# GainDrain.net
KiCad netlist of a schematic drawn in Altium Designer
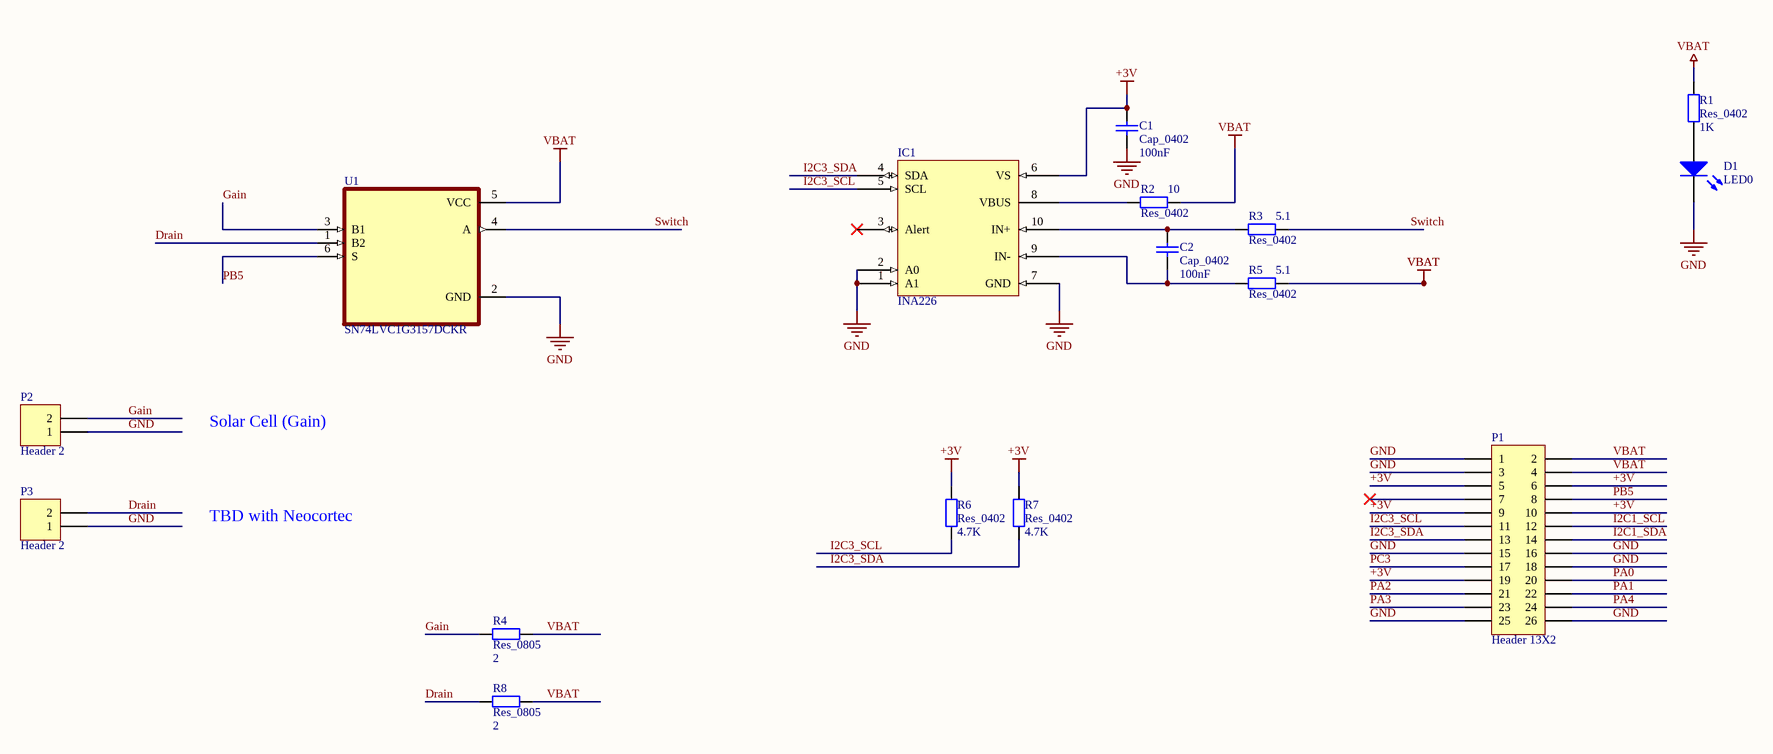
[diagram p0: GainDrain.SchDoc]

(export (version "E")
  (design (tool "Eeschema 10.0.6"))
  (components
    (comp (ref "C1")
      (value "Cap_0402")
      (footprint "0402")
      (description "Capacitor")
      (fields (field (name "ALTIUM_VALUE") "100nF") (field (name "PUBLISHER") "Altium Limited"))
      (libsource (lib "Schematic_Components") (part "Cap_0402"))
    )
    (comp (ref "C2")
      (value "Cap_0402")
      (footprint "0402")
      (description "Capacitor")
      (fields (field (name "ALTIUM_VALUE") "100nF") (field (name "PUBLISHER") "Altium Limited"))
      (libsource (lib "Schematic_Components") (part "Cap_0402"))
    )
    (comp (ref "D1")
      (value "LED0")
      (footprint "0603")
      (description "Typical INFRARED GaAs LED")
      (fields (field (name "PUBLISHER") "Altium Limited"))
      (libsource (lib "Schematic_Components") (part "LED0"))
    )
    (comp (ref "IC1")
      (value "INA226")
      (footprint "VSSOP-10")
      (description "Bi-Directional Current and Power Monitor")
      (libsource (lib "Schematic_Components") (part "INA226"))
    )
    (comp (ref "P1")
      (value "Header 13X2")
      (footprint "HDR2X13")
      (description "Header, 13-Pin, Dual row")
      (fields (field (name "PUBLISHER") "Altium Limited"))
      (libsource (lib "Miscellaneous Connectors") (part "Header 13X2"))
    )
    (comp (ref "P2")
      (value "Header 2")
      (footprint "HDR1X2")
      (description "Header, 2-Pin")
      (fields (field (name "PUBLISHER") "Altium Limited"))
      (libsource (lib "Miscellaneous Connectors") (part "Header 2"))
    )
    (comp (ref "P3")
      (value "Header 2")
      (footprint "HDR1X2")
      (description "Header, 2-Pin")
      (fields (field (name "PUBLISHER") "Altium Limited"))
      (libsource (lib "Miscellaneous Connectors") (part "Header 2"))
    )
    (comp (ref "R1")
      (value "Res_0402")
      (footprint "0402")
      (description "Resistor")
      (fields (field (name "ALTIUM_VALUE") "1K") (field (name "PUBLISHER") "Altium Limited"))
      (libsource (lib "Schematic_Components") (part "Res_0402"))
    )
    (comp (ref "R2")
      (value "Res_0402")
      (footprint "0402")
      (description "Resistor")
      (fields (field (name "ALTIUM_VALUE") "10") (field (name "PUBLISHER") "Altium Limited"))
      (libsource (lib "") (part "Res_0402_1"))
    )
    (comp (ref "R3")
      (value "Res_0402")
      (footprint "0402")
      (description "Resistor")
      (fields (field (name "ALTIUM_VALUE") "5.1") (field (name "PUBLISHER") "Altium Limited"))
      (libsource (lib "") (part "Res_0402_1"))
    )
    (comp (ref "R4")
      (value "Res_0805")
      (footprint "0805")
      (description "Resistor")
      (fields (field (name "ALTIUM_VALUE") "2") (field (name "PUBLISHER") "Altium Limited"))
      (libsource (lib "Schematic_Components") (part "Res_0805"))
    )
    (comp (ref "R5")
      (value "Res_0402")
      (footprint "0402")
      (description "Resistor")
      (fields (field (name "ALTIUM_VALUE") "5.1") (field (name "PUBLISHER") "Altium Limited"))
      (libsource (lib "") (part "Res_0402_1"))
    )
    (comp (ref "R6")
      (value "Res_0402")
      (footprint "0402")
      (description "Resistor")
      (fields (field (name "ALTIUM_VALUE") "4.7K") (field (name "PUBLISHER") "Altium Limited"))
      (libsource (lib "Schematic_Components") (part "Res_0402"))
    )
    (comp (ref "R7")
      (value "Res_0402")
      (footprint "0402")
      (description "Resistor")
      (fields (field (name "ALTIUM_VALUE") "4.7K") (field (name "PUBLISHER") "Altium Limited"))
      (libsource (lib "Schematic_Components") (part "Res_0402"))
    )
    (comp (ref "R8")
      (value "Res_0805")
      (footprint "0805")
      (description "Resistor")
      (fields (field (name "ALTIUM_VALUE") "2") (field (name "PUBLISHER") "Altium Limited"))
      (libsource (lib "Schematic_Components") (part "Res_0805"))
    )
    (comp (ref "U1")
      (value "SN74LVC1G3157DCKR")
      (footprint "SOT65P210X110-6N")
      (description "5 Vï¼Œ2ï¼š1ï¼ˆSPDTï¼‰ï¼Œ1é€šé“é€šç”¨æ¨¡æ“¬é–‹é—œ6-SC70 -40è‡³125")
      (fields (field (name "MF") "Texas Instruments"))
      (libsource (lib "SN74LVC1G3157DCKR") (part "SN74LVC1G3157DCKR"))
    )
  )
  (nets
    (net (code "1") (name "+3V") (class "Default")
      (node (ref "C1") (pin "2") (pinfunction "2_2") (pintype "passive"))
      (node (ref "IC1") (pin "6") (pinfunction "VS_6") (pintype "input"))
      (node (ref "P1") (pin "10") (pinfunction "10_10") (pintype "passive"))
      (node (ref "P1") (pin "19") (pinfunction "19_19") (pintype "passive"))
      (node (ref "P1") (pin "5") (pinfunction "5_5") (pintype "passive"))
      (node (ref "P1") (pin "6") (pinfunction "6_6") (pintype "passive"))
      (node (ref "P1") (pin "9") (pinfunction "9_9") (pintype "passive"))
      (node (ref "R6") (pin "2") (pinfunction "2_2") (pintype "passive"))
      (node (ref "R7") (pin "2") (pinfunction "2_2") (pintype "passive"))
    )
    (net (code "2") (name "/Drain") (class "Default")
      (node (ref "P3") (pin "2") (pinfunction "2_2") (pintype "passive"))
      (node (ref "R8") (pin "2") (pinfunction "2_2") (pintype "passive"))
      (node (ref "U1") (pin "1") (pinfunction "B2_1") (pintype "input"))
    )
    (net (code "3") (name "/Gain") (class "Default")
      (node (ref "P2") (pin "2") (pinfunction "2_2") (pintype "passive"))
      (node (ref "R4") (pin "2") (pinfunction "2_2") (pintype "passive"))
      (node (ref "U1") (pin "3") (pinfunction "B1_3") (pintype "input"))
    )
    (net (code "4") (name "/I2C1_SCL") (class "Default")
      (node (ref "P1") (pin "12") (pinfunction "12_12") (pintype "passive"))
    )
    (net (code "5") (name "/I2C1_SDA") (class "Default")
      (node (ref "P1") (pin "14") (pinfunction "14_14") (pintype "passive"))
    )
    (net (code "6") (name "/I2C3_SCL") (class "Default")
      (node (ref "IC1") (pin "5") (pinfunction "SCL_5") (pintype "input"))
      (node (ref "P1") (pin "11") (pinfunction "11_11") (pintype "passive"))
      (node (ref "R6") (pin "1") (pinfunction "1_1") (pintype "passive"))
    )
    (net (code "7") (name "/I2C3_SDA") (class "Default")
      (node (ref "IC1") (pin "4") (pinfunction "SDA_4") (pintype "bidirectional"))
      (node (ref "P1") (pin "13") (pinfunction "13_13") (pintype "passive"))
      (node (ref "R7") (pin "1") (pinfunction "1_1") (pintype "passive"))
    )
    (net (code "8") (name "/PA0") (class "Default")
      (node (ref "P1") (pin "20") (pinfunction "20_20") (pintype "passive"))
    )
    (net (code "9") (name "/PA1") (class "Default")
      (node (ref "P1") (pin "22") (pinfunction "22_22") (pintype "passive"))
    )
    (net (code "10") (name "/PA2") (class "Default")
      (node (ref "P1") (pin "21") (pinfunction "21_21") (pintype "passive"))
    )
    (net (code "11") (name "/PA3") (class "Default")
      (node (ref "P1") (pin "23") (pinfunction "23_23") (pintype "passive"))
    )
    (net (code "12") (name "/PA4") (class "Default")
      (node (ref "P1") (pin "24") (pinfunction "24_24") (pintype "passive"))
    )
    (net (code "13") (name "/PB5") (class "Default")
      (node (ref "P1") (pin "8") (pinfunction "8_8") (pintype "passive"))
      (node (ref "U1") (pin "6") (pinfunction "S_6") (pintype "input"))
    )
    (net (code "14") (name "/PC3") (class "Default")
      (node (ref "P1") (pin "17") (pinfunction "17_17") (pintype "passive"))
    )
    (net (code "15") (name "/Switch") (class "Default")
      (node (ref "R3") (pin "2") (pinfunction "2_2") (pintype "passive"))
      (node (ref "U1") (pin "4") (pinfunction "A_4") (pintype "output"))
    )
    (net (code "16") (name "GND") (class "Default")
      (node (ref "C1") (pin "1") (pinfunction "1_1") (pintype "passive"))
      (node (ref "D1") (pin "1") (pinfunction "K_1") (pintype "passive"))
      (node (ref "IC1") (pin "1") (pinfunction "A1_1") (pintype "input"))
      (node (ref "IC1") (pin "2") (pinfunction "A0_2") (pintype "input"))
      (node (ref "IC1") (pin "7") (pinfunction "GND_7") (pintype "input"))
      (node (ref "P1") (pin "1") (pinfunction "1_1") (pintype "passive"))
      (node (ref "P1") (pin "15") (pinfunction "15_15") (pintype "passive"))
      (node (ref "P1") (pin "16") (pinfunction "16_16") (pintype "passive"))
      (node (ref "P1") (pin "18") (pinfunction "18_18") (pintype "passive"))
      (node (ref "P1") (pin "25") (pinfunction "25_25") (pintype "passive"))
      (node (ref "P1") (pin "26") (pinfunction "26_26") (pintype "passive"))
      (node (ref "P1") (pin "3") (pinfunction "3_3") (pintype "passive"))
      (node (ref "P2") (pin "1") (pinfunction "1_1") (pintype "passive"))
      (node (ref "P3") (pin "1") (pinfunction "1_1") (pintype "passive"))
      (node (ref "U1") (pin "2") (pinfunction "GND_2") (pintype "power_in"))
    )
    (net (code "17") (name "Net-(D1-A)") (class "Default")
      (node (ref "D1") (pin "2") (pinfunction "A_2") (pintype "passive"))
      (node (ref "R1") (pin "1") (pinfunction "1_1") (pintype "passive"))
    )
    (net (code "18") (name "Net-(IC1-IN+)") (class "Default")
      (node (ref "C2") (pin "2") (pinfunction "2_2") (pintype "passive"))
      (node (ref "IC1") (pin "10") (pinfunction "IN+_10") (pintype "input"))
      (node (ref "R3") (pin "1") (pinfunction "1_1") (pintype "passive"))
    )
    (net (code "19") (name "Net-(IC1-IN-)") (class "Default")
      (node (ref "C2") (pin "1") (pinfunction "1_1") (pintype "passive"))
      (node (ref "IC1") (pin "9") (pinfunction "IN-_9") (pintype "input"))
      (node (ref "R5") (pin "1") (pinfunction "1_1") (pintype "passive"))
    )
    (net (code "20") (name "Net-(IC1-VBUS)") (class "Default")
      (node (ref "IC1") (pin "8") (pinfunction "VBUS_8") (pintype "power_in"))
      (node (ref "R2") (pin "1") (pinfunction "1_1") (pintype "passive"))
    )
    (net (code "21") (name "VBAT") (class "Default")
      (node (ref "P1") (pin "2") (pinfunction "2_2") (pintype "passive"))
      (node (ref "P1") (pin "4") (pinfunction "4_4") (pintype "passive"))
      (node (ref "R1") (pin "2") (pinfunction "2_2") (pintype "passive"))
      (node (ref "R2") (pin "2") (pinfunction "2_2") (pintype "passive"))
      (node (ref "R4") (pin "1") (pinfunction "1_1") (pintype "passive"))
      (node (ref "R5") (pin "2") (pinfunction "2_2") (pintype "passive"))
      (node (ref "R8") (pin "1") (pinfunction "1_1") (pintype "passive"))
      (node (ref "U1") (pin "5") (pinfunction "VCC_5") (pintype "power_in"))
    )
    (net (code "22") (name "unconnected-(IC1-Alert-Pad3)") (class "Default")
      (node (ref "IC1") (pin "3") (pinfunction "Alert_3") (pintype "bidirectional+no_connect"))
    )
    (net (code "23") (name "unconnected-(P1-Pad7)") (class "Default")
      (node (ref "P1") (pin "7") (pinfunction "7_7") (pintype "passive+no_connect"))
    )
  )
)
